# servoyolu_5servo.net
KiCad netlist of a schematic drawn in EAGLE
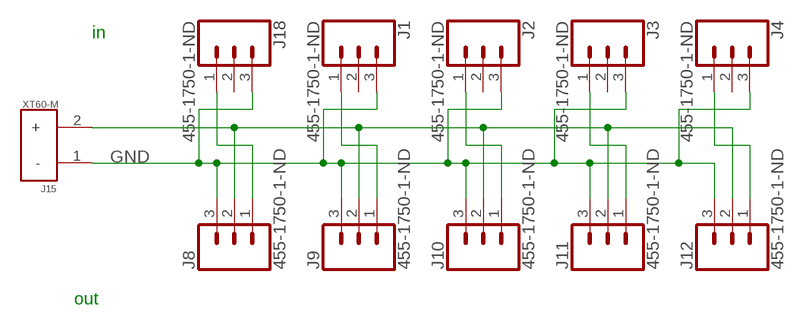
[diagram p0: schematic, sheet 1]

(export (version "E")
  (design (tool "Eeschema 10.0.6"))
  (components
    (comp (ref "J1")
      (value "455-1750-1-ND")
      (footprint "eagle-import:1X03")
      (libsource (lib "eagle-import") (part "CONN_03"))
    )
    (comp (ref "J2")
      (value "455-1750-1-ND")
      (footprint "eagle-import:1X03")
      (libsource (lib "eagle-import") (part "CONN_03"))
    )
    (comp (ref "J3")
      (value "455-1750-1-ND")
      (footprint "eagle-import:1X03")
      (libsource (lib "eagle-import") (part "CONN_03"))
    )
    (comp (ref "J4")
      (value "455-1750-1-ND")
      (footprint "eagle-import:1X03")
      (libsource (lib "eagle-import") (part "CONN_03"))
    )
    (comp (ref "J8")
      (value "455-1750-1-ND")
      (footprint "eagle-import:1X03")
      (libsource (lib "eagle-import") (part "CONN_03"))
    )
    (comp (ref "J9")
      (value "455-1750-1-ND")
      (footprint "eagle-import:1X03")
      (libsource (lib "eagle-import") (part "CONN_03"))
    )
    (comp (ref "J10")
      (value "455-1750-1-ND")
      (footprint "eagle-import:1X03")
      (libsource (lib "eagle-import") (part "CONN_03"))
    )
    (comp (ref "J11")
      (value "455-1750-1-ND")
      (footprint "eagle-import:1X03")
      (libsource (lib "eagle-import") (part "CONN_03"))
    )
    (comp (ref "J12")
      (value "455-1750-1-ND")
      (footprint "eagle-import:1X03")
      (libsource (lib "eagle-import") (part "CONN_03"))
    )
    (comp (ref "J15")
      (value "XT60-M")
      (footprint "eagle-import:AMASS_XT60-M")
      (fields (field (name "MF") "AMASS"))
      (libsource (lib "eagle-import") (part "XT60-M"))
    )
    (comp (ref "J18")
      (value "455-1750-1-ND")
      (footprint "eagle-import:1X03")
      (libsource (lib "eagle-import") (part "CONN_03"))
    )
  )
  (nets
    (net (code "1") (name "/GND") (class "Default")
      (node (ref "J1") (pin "3") (pinfunction "3_3") (pintype "passive"))
      (node (ref "J10") (pin "3") (pinfunction "3_3") (pintype "passive"))
      (node (ref "J11") (pin "3") (pinfunction "3_3") (pintype "passive"))
      (node (ref "J12") (pin "3") (pinfunction "3_3") (pintype "passive"))
      (node (ref "J15") (pin "1") (pinfunction "-_1") (pintype "passive"))
      (node (ref "J18") (pin "3") (pinfunction "3_3") (pintype "passive"))
      (node (ref "J2") (pin "3") (pinfunction "3_3") (pintype "passive"))
      (node (ref "J3") (pin "3") (pinfunction "3_3") (pintype "passive"))
      (node (ref "J4") (pin "3") (pinfunction "3_3") (pintype "passive"))
      (node (ref "J8") (pin "3") (pinfunction "3_3") (pintype "passive"))
      (node (ref "J9") (pin "3") (pinfunction "3_3") (pintype "passive"))
    )
    (net (code "2") (name "Net-(J1-Pad1)") (class "Default")
      (node (ref "J1") (pin "1") (pinfunction "1_1") (pintype "passive"))
      (node (ref "J9") (pin "1") (pinfunction "1_1") (pintype "passive"))
    )
    (net (code "3") (name "Net-(J10-Pad1)") (class "Default")
      (node (ref "J10") (pin "1") (pinfunction "1_1") (pintype "passive"))
      (node (ref "J2") (pin "1") (pinfunction "1_1") (pintype "passive"))
    )
    (net (code "4") (name "Net-(J11-Pad1)") (class "Default")
      (node (ref "J11") (pin "1") (pinfunction "1_1") (pintype "passive"))
      (node (ref "J3") (pin "1") (pinfunction "1_1") (pintype "passive"))
    )
    (net (code "5") (name "Net-(J12-Pad1)") (class "Default")
      (node (ref "J12") (pin "1") (pinfunction "1_1") (pintype "passive"))
      (node (ref "J4") (pin "1") (pinfunction "1_1") (pintype "passive"))
    )
    (net (code "6") (name "Net-(J15-+)") (class "Default")
      (node (ref "J10") (pin "2") (pinfunction "2_2") (pintype "passive"))
      (node (ref "J11") (pin "2") (pinfunction "2_2") (pintype "passive"))
      (node (ref "J12") (pin "2") (pinfunction "2_2") (pintype "passive"))
      (node (ref "J15") (pin "2") (pinfunction "+_2") (pintype "passive"))
      (node (ref "J8") (pin "2") (pinfunction "2_2") (pintype "passive"))
      (node (ref "J9") (pin "2") (pinfunction "2_2") (pintype "passive"))
    )
    (net (code "7") (name "Net-(J18-Pad1)") (class "Default")
      (node (ref "J18") (pin "1") (pinfunction "1_1") (pintype "passive"))
      (node (ref "J8") (pin "1") (pinfunction "1_1") (pintype "passive"))
    )
    (net (code "8") (name "unconnected-(J1-Pad2)") (class "Default")
      (node (ref "J1") (pin "2") (pinfunction "2_2") (pintype "passive"))
    )
    (net (code "9") (name "unconnected-(J2-Pad2)") (class "Default")
      (node (ref "J2") (pin "2") (pinfunction "2_2") (pintype "passive"))
    )
    (net (code "10") (name "unconnected-(J3-Pad2)") (class "Default")
      (node (ref "J3") (pin "2") (pinfunction "2_2") (pintype "passive"))
    )
    (net (code "11") (name "unconnected-(J4-Pad2)") (class "Default")
      (node (ref "J4") (pin "2") (pinfunction "2_2") (pintype "passive"))
    )
    (net (code "12") (name "unconnected-(J18-Pad2)") (class "Default")
      (node (ref "J18") (pin "2") (pinfunction "2_2") (pintype "passive"))
    )
  )
)
